# cpu.net
KiCad netlist of a schematic drawn in Altium Designer
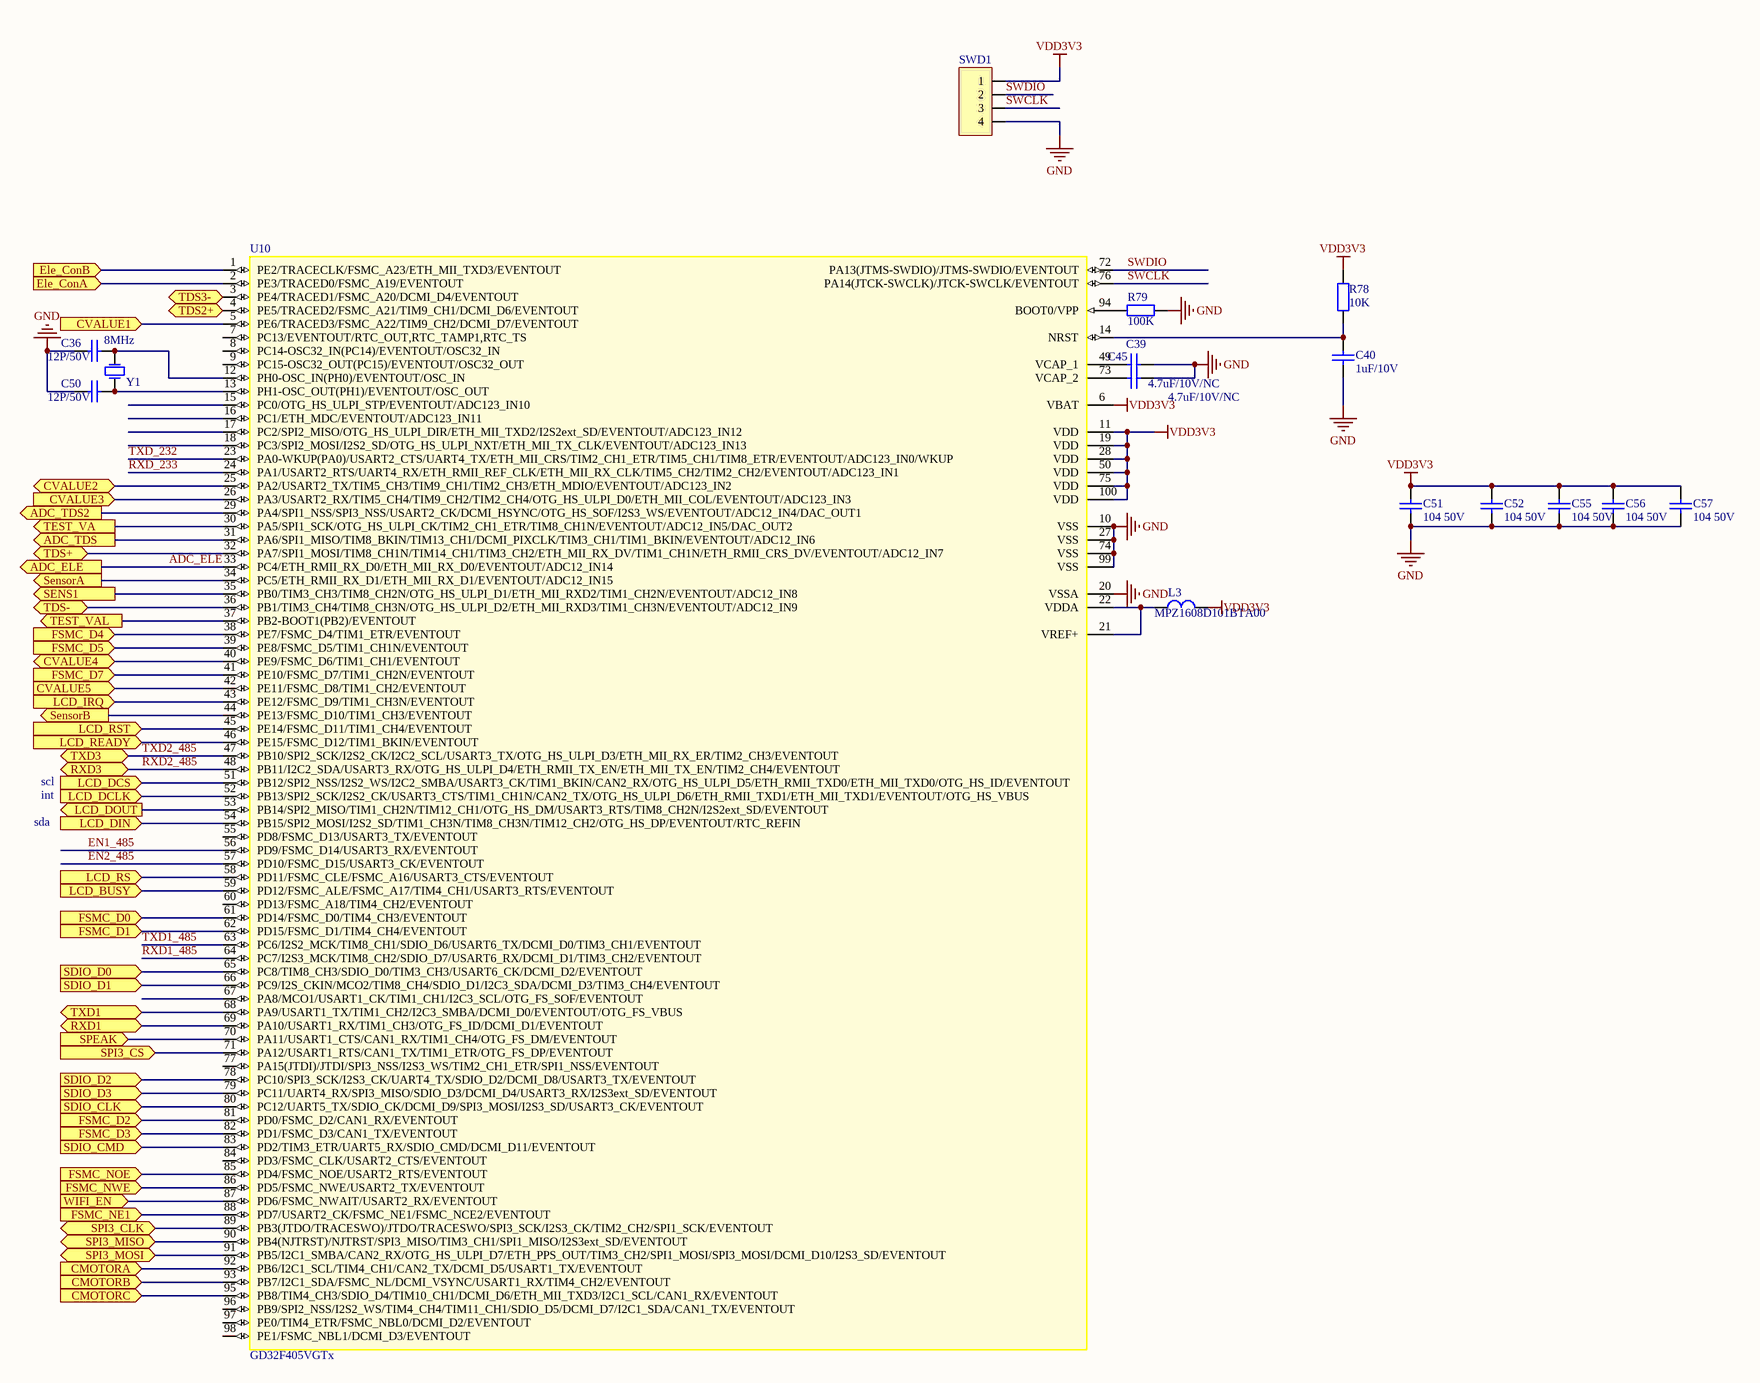
[diagram p0: cpu.SchDoc]

(export (version "E")
  (design (tool "Eeschema 10.0.6"))
  (components
    (comp (ref "C36")
      (value "12P/50V")
      (footprint "SMD-0603C")
      (description "贴片电容 5%")
      (libsource (lib "XiaoyI") (part "CAP4"))
    )
    (comp (ref "C39")
      (value "4.7uF/10V/NC")
      (footprint "SMD-0603C")
      (description "贴片电容 20%")
      (libsource (lib "XiaoyI") (part "CAP4"))
    )
    (comp (ref "C40")
      (value "1uF/10V")
      (footprint "SMD-0603C")
      (description "贴片电容 20%")
      (libsource (lib "XiaoyI") (part "CAP4"))
    )
    (comp (ref "C45")
      (value "4.7uF/10V/NC")
      (footprint "SMD-0603C")
      (description "贴片电容 20%")
      (libsource (lib "XiaoyI") (part "CAP4"))
    )
    (comp (ref "C50")
      (value "12P/50V")
      (footprint "SMD-0603C")
      (description "贴片电容 5%")
      (libsource (lib "XiaoyI") (part "CAP4"))
    )
    (comp (ref "C51")
      (value "104 50V")
      (footprint "SMD-0603C")
      (description "贴片电容 20%")
      (libsource (lib "XiaoyI") (part "CAP4"))
    )
    (comp (ref "C52")
      (value "104 50V")
      (footprint "SMD-0603C")
      (description "贴片电容 20%")
      (libsource (lib "XiaoyI") (part "CAP4"))
    )
    (comp (ref "C55")
      (value "104 50V")
      (footprint "SMD-0603C")
      (description "贴片电容 20%")
      (libsource (lib "XiaoyI") (part "CAP4"))
    )
    (comp (ref "C56")
      (value "104 50V")
      (footprint "SMD-0603C")
      (description "贴片电容 20%")
      (libsource (lib "XiaoyI") (part "CAP4"))
    )
    (comp (ref "C57")
      (value "104 50V")
      (footprint "SMD-0603C")
      (description "贴片电容 20%")
      (libsource (lib "XiaoyI") (part "CAP4"))
    )
    (comp (ref "L3")
      (value "MPZ1608D101BTA00")
      (footprint "SMD-0603")
      (description "磁珠电感 100R 100MHz")
      (libsource (lib "XiaoyI") (part "CIZHU1"))
    )
    (comp (ref "R78")
      (value "10K")
      (footprint "SMD-0603")
      (description "贴片电阻 5%")
      (libsource (lib "") (part "RES2_1"))
    )
    (comp (ref "R79")
      (value "100K")
      (footprint "SMD-0603")
      (description "贴片电阻 5%")
      (libsource (lib "XiaoyI") (part "RES2"))
    )
    (comp (ref "SWD1")
      (value "SIP-4 (NC)")
      (footprint "SIP-4")
      (description "ISP 下载")
      (libsource (lib "XiaoyI") (part "SIP-4"))
    )
    (comp (ref "U10")
      (value "GD32F405VGTx")
      (footprint "STM-LQFP100_N")
      (fields (field (name "MANUFACTURER") "STMicroelectronics") (field (name "PARTNUMBER") "STM32F405VGT6"))
      (libsource (lib "STM32F4") (part "STM32F405VGTx"))
    )
    (comp (ref "Y1")
      (value "8MHz")
      (footprint "XTAL-3225-2")
      (description "3225 贴片晶振")
      (libsource (lib "XiaoyI") (part "XTAL"))
    )
  )
  (nets
    (net (code "1") (name "/ADC_ELE") (class "Default")
      (node (ref "U10") (pin "33") (pinfunction "PC4/ETH_RMII_RX_D0/ETH_MII_RX_D0/EVENTOUT/ADC12_IN14_33") (pintype "bidirectional"))
    )
    (net (code "2") (name "/ADC_TDS") (class "Default")
      (node (ref "U10") (pin "31") (pinfunction "PA6/SPI1_MISO/TIM8_BKIN/TIM13_CH1/DCMI_PIXCLK/TIM3_CH1/TIM1_BKIN/EVENTOUT/ADC12_IN6_31") (pintype "bidirectional"))
    )
    (net (code "3") (name "/ADC_TDS2") (class "Default")
      (node (ref "U10") (pin "29") (pinfunction "PA4/SPI1_NSS/SPI3_NSS/USART2_CK/DCMI_HSYNC/OTG_HS_SOF/I2S3_WS/EVENTOUT/ADC12_IN4/DAC_OUT1_29") (pintype "bidirectional"))
    )
    (net (code "4") (name "/CMOTORA") (class "Default")
      (node (ref "U10") (pin "92") (pinfunction "PB6/I2C1_SCL/TIM4_CH1/CAN2_TX/DCMI_D5/USART1_TX/EVENTOUT_92") (pintype "bidirectional"))
    )
    (net (code "5") (name "/CMOTORB") (class "Default")
      (node (ref "U10") (pin "93") (pinfunction "PB7/I2C1_SDA/FSMC_NL/DCMI_VSYNC/USART1_RX/TIM4_CH2/EVENTOUT_93") (pintype "bidirectional"))
    )
    (net (code "6") (name "/CMOTORC") (class "Default")
      (node (ref "U10") (pin "95") (pinfunction "PB8/TIM4_CH3/SDIO_D4/TIM10_CH1/DCMI_D6/ETH_MII_TXD3/I2C1_SCL/CAN1_RX/EVENTOUT_95") (pintype "bidirectional"))
    )
    (net (code "7") (name "/CVALUE1") (class "Default")
      (node (ref "U10") (pin "5") (pinfunction "PE6/TRACED3/FSMC_A22/TIM9_CH2/DCMI_D7/EVENTOUT_5") (pintype "bidirectional"))
    )
    (net (code "8") (name "/CVALUE2") (class "Default")
      (node (ref "U10") (pin "25") (pinfunction "PA2/USART2_TX/TIM5_CH3/TIM9_CH1/TIM2_CH3/ETH_MDIO/EVENTOUT/ADC123_IN2_25") (pintype "bidirectional"))
    )
    (net (code "9") (name "/CVALUE3") (class "Default")
      (node (ref "U10") (pin "26") (pinfunction "PA3/USART2_RX/TIM5_CH4/TIM9_CH2/TIM2_CH4/OTG_HS_ULPI_D0/ETH_MII_COL/EVENTOUT/ADC123_IN3_26") (pintype "bidirectional"))
    )
    (net (code "10") (name "/CVALUE4") (class "Default")
      (node (ref "U10") (pin "40") (pinfunction "PE9/FSMC_D6/TIM1_CH1/EVENTOUT_40") (pintype "bidirectional"))
    )
    (net (code "11") (name "/CVALUE5") (class "Default")
      (node (ref "U10") (pin "42") (pinfunction "PE11/FSMC_D8/TIM1_CH2/EVENTOUT_42") (pintype "bidirectional"))
    )
    (net (code "12") (name "/EN1_485") (class "Default")
      (node (ref "U10") (pin "56") (pinfunction "PD9/FSMC_D14/USART3_RX/EVENTOUT_56") (pintype "bidirectional"))
    )
    (net (code "13") (name "/EN2_485") (class "Default")
      (node (ref "U10") (pin "57") (pinfunction "PD10/FSMC_D15/USART3_CK/EVENTOUT_57") (pintype "bidirectional"))
    )
    (net (code "14") (name "/Ele_ConA") (class "Default")
      (node (ref "U10") (pin "2") (pinfunction "PE3/TRACED0/FSMC_A19/EVENTOUT_2") (pintype "bidirectional"))
    )
    (net (code "15") (name "/Ele_ConB") (class "Default")
      (node (ref "U10") (pin "1") (pinfunction "PE2/TRACECLK/FSMC_A23/ETH_MII_TXD3/EVENTOUT_1") (pintype "bidirectional"))
    )
    (net (code "16") (name "/FSMC_D0") (class "Default")
      (node (ref "U10") (pin "61") (pinfunction "PD14/FSMC_D0/TIM4_CH3/EVENTOUT_61") (pintype "bidirectional"))
    )
    (net (code "17") (name "/FSMC_D1") (class "Default")
      (node (ref "U10") (pin "62") (pinfunction "PD15/FSMC_D1/TIM4_CH4/EVENTOUT_62") (pintype "bidirectional"))
    )
    (net (code "18") (name "/FSMC_D2") (class "Default")
      (node (ref "U10") (pin "81") (pinfunction "PD0/FSMC_D2/CAN1_RX/EVENTOUT_81") (pintype "bidirectional"))
    )
    (net (code "19") (name "/FSMC_D3") (class "Default")
      (node (ref "U10") (pin "82") (pinfunction "PD1/FSMC_D3/CAN1_TX/EVENTOUT_82") (pintype "bidirectional"))
    )
    (net (code "20") (name "/FSMC_D4") (class "Default")
      (node (ref "U10") (pin "38") (pinfunction "PE7/FSMC_D4/TIM1_ETR/EVENTOUT_38") (pintype "bidirectional"))
    )
    (net (code "21") (name "/FSMC_D5") (class "Default")
      (node (ref "U10") (pin "39") (pinfunction "PE8/FSMC_D5/TIM1_CH1N/EVENTOUT_39") (pintype "bidirectional"))
    )
    (net (code "22") (name "/FSMC_D7") (class "Default")
      (node (ref "U10") (pin "41") (pinfunction "PE10/FSMC_D7/TIM1_CH2N/EVENTOUT_41") (pintype "bidirectional"))
    )
    (net (code "23") (name "/FSMC_NE1") (class "Default")
      (node (ref "U10") (pin "88") (pinfunction "PD7/USART2_CK/FSMC_NE1/FSMC_NCE2/EVENTOUT_88") (pintype "bidirectional"))
    )
    (net (code "24") (name "/FSMC_NOE") (class "Default")
      (node (ref "U10") (pin "85") (pinfunction "PD4/FSMC_NOE/USART2_RTS/EVENTOUT_85") (pintype "bidirectional"))
    )
    (net (code "25") (name "/FSMC_NWE") (class "Default")
      (node (ref "U10") (pin "86") (pinfunction "PD5/FSMC_NWE/USART2_TX/EVENTOUT_86") (pintype "bidirectional"))
    )
    (net (code "26") (name "/LCD_BUSY") (class "Default")
      (node (ref "U10") (pin "59") (pinfunction "PD12/FSMC_ALE/FSMC_A17/TIM4_CH1/USART3_RTS/EVENTOUT_59") (pintype "bidirectional"))
    )
    (net (code "27") (name "/LCD_DCLK") (class "Default")
      (node (ref "U10") (pin "52") (pinfunction "PB13/SPI2_SCK/I2S2_CK/USART3_CTS/TIM1_CH1N/CAN2_TX/OTG_HS_ULPI_D6/ETH_RMII_TXD1/ETH_MII_TXD1/EVENTOUT/OTG_HS_VBUS_52") (pintype "bidirectional"))
    )
    (net (code "28") (name "/LCD_DCS") (class "Default")
      (node (ref "U10") (pin "51") (pinfunction "PB12/SPI2_NSS/I2S2_WS/I2C2_SMBA/USART3_CK/TIM1_BKIN/CAN2_RX/OTG_HS_ULPI_D5/ETH_RMII_TXD0/ETH_MII_TXD0/OTG_HS_ID/EVENTOUT_51") (pintype "bidirectional"))
    )
    (net (code "29") (name "/LCD_DIN") (class "Default")
      (node (ref "U10") (pin "54") (pinfunction "PB15/SPI2_MOSI/I2S2_SD/TIM1_CH3N/TIM8_CH3N/TIM12_CH2/OTG_HS_DP/EVENTOUT/RTC_REFIN_54") (pintype "bidirectional"))
    )
    (net (code "30") (name "/LCD_DOUT") (class "Default")
      (node (ref "U10") (pin "53") (pinfunction "PB14/SPI2_MISO/TIM1_CH2N/TIM12_CH1/OTG_HS_DM/USART3_RTS/TIM8_CH2N/I2S2ext_SD/EVENTOUT_53") (pintype "bidirectional"))
    )
    (net (code "31") (name "/LCD_IRQ") (class "Default")
      (node (ref "U10") (pin "43") (pinfunction "PE12/FSMC_D9/TIM1_CH3N/EVENTOUT_43") (pintype "bidirectional"))
    )
    (net (code "32") (name "/LCD_READY") (class "Default")
      (node (ref "U10") (pin "46") (pinfunction "PE15/FSMC_D12/TIM1_BKIN/EVENTOUT_46") (pintype "bidirectional"))
    )
    (net (code "33") (name "/LCD_RS") (class "Default")
      (node (ref "U10") (pin "58") (pinfunction "PD11/FSMC_CLE/FSMC_A16/USART3_CTS/EVENTOUT_58") (pintype "bidirectional"))
    )
    (net (code "34") (name "/LCD_RST") (class "Default")
      (node (ref "U10") (pin "45") (pinfunction "PE14/FSMC_D11/TIM1_CH4/EVENTOUT_45") (pintype "bidirectional"))
    )
    (net (code "35") (name "/RXD1") (class "Default")
      (node (ref "U10") (pin "69") (pinfunction "PA10/USART1_RX/TIM1_CH3/OTG_FS_ID/DCMI_D1/EVENTOUT_69") (pintype "bidirectional"))
    )
    (net (code "36") (name "/RXD1_485") (class "Default")
      (node (ref "U10") (pin "64") (pinfunction "PC7/I2S3_MCK/TIM8_CH2/SDIO_D7/USART6_RX/DCMI_D1/TIM3_CH2/EVENTOUT_64") (pintype "bidirectional"))
    )
    (net (code "37") (name "/RXD2_485") (class "Default")
      (node (ref "U10") (pin "48") (pinfunction "PB11/I2C2_SDA/USART3_RX/OTG_HS_ULPI_D4/ETH_RMII_TX_EN/ETH_MII_TX_EN/TIM2_CH4/EVENTOUT_48") (pintype "bidirectional"))
    )
    (net (code "38") (name "/RXD_233") (class "Default")
      (node (ref "U10") (pin "24") (pinfunction "PA1/USART2_RTS/UART4_RX/ETH_RMII_REF_CLK/ETH_MII_RX_CLK/TIM5_CH2/TIM2_CH2/EVENTOUT/ADC123_IN1_24") (pintype "bidirectional"))
    )
    (net (code "39") (name "/SDIO_CLK") (class "Default")
      (node (ref "U10") (pin "80") (pinfunction "PC12/UART5_TX/SDIO_CK/DCMI_D9/SPI3_MOSI/I2S3_SD/USART3_CK/EVENTOUT_80") (pintype "bidirectional"))
    )
    (net (code "40") (name "/SDIO_CMD") (class "Default")
      (node (ref "U10") (pin "83") (pinfunction "PD2/TIM3_ETR/UART5_RX/SDIO_CMD/DCMI_D11/EVENTOUT_83") (pintype "bidirectional"))
    )
    (net (code "41") (name "/SDIO_D0") (class "Default")
      (node (ref "U10") (pin "65") (pinfunction "PC8/TIM8_CH3/SDIO_D0/TIM3_CH3/USART6_CK/DCMI_D2/EVENTOUT_65") (pintype "bidirectional"))
    )
    (net (code "42") (name "/SDIO_D1") (class "Default")
      (node (ref "U10") (pin "66") (pinfunction "PC9/I2S_CKIN/MCO2/TIM8_CH4/SDIO_D1/I2C3_SDA/DCMI_D3/TIM3_CH4/EVENTOUT_66") (pintype "bidirectional"))
    )
    (net (code "43") (name "/SDIO_D2") (class "Default")
      (node (ref "U10") (pin "78") (pinfunction "PC10/SPI3_SCK/I2S3_CK/UART4_TX/SDIO_D2/DCMI_D8/USART3_TX/EVENTOUT_78") (pintype "bidirectional"))
    )
    (net (code "44") (name "/SDIO_D3") (class "Default")
      (node (ref "U10") (pin "79") (pinfunction "PC11/UART4_RX/SPI3_MISO/SDIO_D3/DCMI_D4/USART3_RX/I2S3ext_SD/EVENTOUT_79") (pintype "bidirectional"))
    )
    (net (code "45") (name "/SENS1") (class "Default")
      (node (ref "U10") (pin "35") (pinfunction "PB0/TIM3_CH3/TIM8_CH2N/OTG_HS_ULPI_D1/ETH_MII_RXD2/TIM1_CH2N/EVENTOUT/ADC12_IN8_35") (pintype "bidirectional"))
    )
    (net (code "46") (name "/SPEAK") (class "Default")
      (node (ref "U10") (pin "70") (pinfunction "PA11/USART1_CTS/CAN1_RX/TIM1_CH4/OTG_FS_DM/EVENTOUT_70") (pintype "bidirectional"))
    )
    (net (code "47") (name "/SPI3_CLK") (class "Default")
      (node (ref "U10") (pin "89") (pinfunction "PB3(JTDO/TRACESWO)/JTDO/TRACESWO/SPI3_SCK/I2S3_CK/TIM2_CH2/SPI1_SCK/EVENTOUT_89") (pintype "bidirectional"))
    )
    (net (code "48") (name "/SPI3_CS") (class "Default")
      (node (ref "U10") (pin "71") (pinfunction "PA12/USART1_RTS/CAN1_TX/TIM1_ETR/OTG_FS_DP/EVENTOUT_71") (pintype "bidirectional"))
    )
    (net (code "49") (name "/SPI3_MISO") (class "Default")
      (node (ref "U10") (pin "90") (pinfunction "PB4(NJTRST)/NJTRST/SPI3_MISO/TIM3_CH1/SPI1_MISO/I2S3ext_SD/EVENTOUT_90") (pintype "bidirectional"))
    )
    (net (code "50") (name "/SPI3_MOSI") (class "Default")
      (node (ref "U10") (pin "91") (pinfunction "PB5/I2C1_SMBA/CAN2_RX/OTG_HS_ULPI_D7/ETH_PPS_OUT/TIM3_CH2/SPI1_MOSI/SPI3_MOSI/DCMI_D10/I2S3_SD/EVENTOUT_91") (pintype "bidirectional"))
    )
    (net (code "51") (name "/SWCLK") (class "Default")
      (node (ref "SWD1") (pin "3") (pinfunction "3_3") (pintype "passive"))
      (node (ref "U10") (pin "76") (pinfunction "PA14(JTCK-SWCLK)/JTCK-SWCLK/EVENTOUT_76") (pintype "bidirectional"))
    )
    (net (code "52") (name "/SWDIO") (class "Default")
      (node (ref "SWD1") (pin "2") (pinfunction "2_2") (pintype "passive"))
      (node (ref "U10") (pin "72") (pinfunction "PA13(JTMS-SWDIO)/JTMS-SWDIO/EVENTOUT_72") (pintype "bidirectional"))
    )
    (net (code "53") (name "/SensorA") (class "Default")
      (node (ref "U10") (pin "34") (pinfunction "PC5/ETH_RMII_RX_D1/ETH_MII_RX_D1/EVENTOUT/ADC12_IN15_34") (pintype "bidirectional"))
    )
    (net (code "54") (name "/SensorB") (class "Default")
      (node (ref "U10") (pin "44") (pinfunction "PE13/FSMC_D10/TIM1_CH3/EVENTOUT_44") (pintype "bidirectional"))
    )
    (net (code "55") (name "/TDS+") (class "Default")
      (node (ref "U10") (pin "32") (pinfunction "PA7/SPI1_MOSI/TIM8_CH1N/TIM14_CH1/TIM3_CH2/ETH_MII_RX_DV/TIM1_CH1N/ETH_RMII_CRS_DV/EVENTOUT/ADC12_IN7_32") (pintype "bidirectional"))
    )
    (net (code "56") (name "/TDS-") (class "Default")
      (node (ref "U10") (pin "36") (pinfunction "PB1/TIM3_CH4/TIM8_CH3N/OTG_HS_ULPI_D2/ETH_MII_RXD3/TIM1_CH3N/EVENTOUT/ADC12_IN9_36") (pintype "bidirectional"))
    )
    (net (code "57") (name "/TDS2+") (class "Default")
      (node (ref "U10") (pin "4") (pinfunction "PE5/TRACED2/FSMC_A21/TIM9_CH1/DCMI_D6/EVENTOUT_4") (pintype "bidirectional"))
    )
    (net (code "58") (name "/TDS3-") (class "Default")
      (node (ref "U10") (pin "3") (pinfunction "PE4/TRACED1/FSMC_A20/DCMI_D4/EVENTOUT_3") (pintype "bidirectional"))
    )
    (net (code "59") (name "/TEST_VA") (class "Default")
      (node (ref "U10") (pin "30") (pinfunction "PA5/SPI1_SCK/OTG_HS_ULPI_CK/TIM2_CH1_ETR/TIM8_CH1N/EVENTOUT/ADC12_IN5/DAC_OUT2_30") (pintype "bidirectional"))
    )
    (net (code "60") (name "/TEST_VAL") (class "Default")
      (node (ref "U10") (pin "37") (pinfunction "PB2-BOOT1(PB2)/EVENTOUT_37") (pintype "bidirectional"))
    )
    (net (code "61") (name "/TXD1") (class "Default")
      (node (ref "U10") (pin "68") (pinfunction "PA9/USART1_TX/TIM1_CH2/I2C3_SMBA/DCMI_D0/EVENTOUT/OTG_FS_VBUS_68") (pintype "bidirectional"))
    )
    (net (code "62") (name "/TXD1_485") (class "Default")
      (node (ref "U10") (pin "63") (pinfunction "PC6/I2S2_MCK/TIM8_CH1/SDIO_D6/USART6_TX/DCMI_D0/TIM3_CH1/EVENTOUT_63") (pintype "bidirectional"))
    )
    (net (code "63") (name "/TXD2_485") (class "Default")
      (node (ref "U10") (pin "47") (pinfunction "PB10/SPI2_SCK/I2S2_CK/I2C2_SCL/USART3_TX/OTG_HS_ULPI_D3/ETH_MII_RX_ER/TIM2_CH3/EVENTOUT_47") (pintype "bidirectional"))
    )
    (net (code "64") (name "/TXD_232") (class "Default")
      (node (ref "U10") (pin "23") (pinfunction "PA0-WKUP(PA0)/USART2_CTS/UART4_TX/ETH_MII_CRS/TIM2_CH1_ETR/TIM5_CH1/TIM8_ETR/EVENTOUT/ADC123_IN0/WKUP_23") (pintype "bidirectional"))
    )
    (net (code "65") (name "/WIFI_EN") (class "Default")
      (node (ref "U10") (pin "87") (pinfunction "PD6/FSMC_NWAIT/USART2_RX/EVENTOUT_87") (pintype "bidirectional"))
    )
    (net (code "66") (name "GND") (class "Default")
      (node (ref "C36") (pin "2") (pinfunction "2_2") (pintype "passive"))
      (node (ref "C39") (pin "1") (pinfunction "1_1") (pintype "passive"))
      (node (ref "C40") (pin "1") (pinfunction "1_1") (pintype "passive"))
      (node (ref "C45") (pin "1") (pinfunction "1_1") (pintype "passive"))
      (node (ref "C50") (pin "2") (pinfunction "2_2") (pintype "passive"))
      (node (ref "C51") (pin "1") (pinfunction "1_1") (pintype "passive"))
      (node (ref "C52") (pin "1") (pinfunction "1_1") (pintype "passive"))
      (node (ref "C55") (pin "1") (pinfunction "1_1") (pintype "passive"))
      (node (ref "C56") (pin "1") (pinfunction "1_1") (pintype "passive"))
      (node (ref "C57") (pin "1") (pinfunction "1_1") (pintype "passive"))
      (node (ref "R79") (pin "1") (pinfunction "1_1") (pintype "passive"))
      (node (ref "SWD1") (pin "4") (pinfunction "4_4") (pintype "passive"))
      (node (ref "U10") (pin "10") (pinfunction "VSS_10") (pintype "power_in"))
      (node (ref "U10") (pin "20") (pinfunction "VSSA_20") (pintype "power_in"))
      (node (ref "U10") (pin "27") (pinfunction "VSS_27") (pintype "power_in"))
      (node (ref "U10") (pin "74") (pinfunction "VSS_74") (pintype "power_in"))
      (node (ref "U10") (pin "99") (pinfunction "VSS_99") (pintype "power_in"))
    )
    (net (code "67") (name "Net-(U10-BOOT0{slash}VPP)") (class "Default")
      (node (ref "R79") (pin "2") (pinfunction "2_2") (pintype "passive"))
      (node (ref "U10") (pin "94") (pinfunction "BOOT0/VPP_94") (pintype "input"))
    )
    (net (code "68") (name "Net-(U10-NRST)") (class "Default")
      (node (ref "C40") (pin "2") (pinfunction "2_2") (pintype "passive"))
      (node (ref "R78") (pin "1") (pinfunction "1_1") (pintype "passive"))
      (node (ref "U10") (pin "14") (pinfunction "NRST_14") (pintype "bidirectional"))
    )
    (net (code "69") (name "Net-(U10-PH0-OSC_IN(PH0){slash}EVENTOUT{slash}OSC_IN)") (class "Default")
      (node (ref "C36") (pin "1") (pinfunction "1_1") (pintype "passive"))
      (node (ref "U10") (pin "12") (pinfunction "PH0-OSC_IN(PH0)/EVENTOUT/OSC_IN_12") (pintype "bidirectional"))
      (node (ref "Y1") (pin "2") (pinfunction "OSC2_2") (pintype "passive"))
    )
    (net (code "70") (name "Net-(U10-PH1-OSC_OUT(PH1){slash}EVENTOUT{slash}OSC_OUT)") (class "Default")
      (node (ref "C50") (pin "1") (pinfunction "1_1") (pintype "passive"))
      (node (ref "U10") (pin "13") (pinfunction "PH1-OSC_OUT(PH1)/EVENTOUT/OSC_OUT_13") (pintype "bidirectional"))
      (node (ref "Y1") (pin "1") (pinfunction "OSC1_1") (pintype "passive"))
    )
    (net (code "71") (name "Net-(U10-VCAP_1)") (class "Default")
      (node (ref "C39") (pin "2") (pinfunction "2_2") (pintype "passive"))
      (node (ref "U10") (pin "49") (pinfunction "VCAP_1_49") (pintype "power_in"))
    )
    (net (code "72") (name "Net-(U10-VCAP_2)") (class "Default")
      (node (ref "C45") (pin "2") (pinfunction "2_2") (pintype "passive"))
      (node (ref "U10") (pin "73") (pinfunction "VCAP_2_73") (pintype "power_in"))
    )
    (net (code "73") (name "Net-(U10-VDDA)") (class "Default")
      (node (ref "L3") (pin "2") (pinfunction "2_2") (pintype "passive"))
      (node (ref "U10") (pin "21") (pinfunction "VREF+_21") (pintype "power_in"))
      (node (ref "U10") (pin "22") (pinfunction "VDDA_22") (pintype "power_in"))
    )
    (net (code "74") (name "VDD3V3") (class "Default")
      (node (ref "C51") (pin "2") (pinfunction "2_2") (pintype "passive"))
      (node (ref "C52") (pin "2") (pinfunction "2_2") (pintype "passive"))
      (node (ref "C55") (pin "2") (pinfunction "2_2") (pintype "passive"))
      (node (ref "C56") (pin "2") (pinfunction "2_2") (pintype "passive"))
      (node (ref "C57") (pin "2") (pinfunction "2_2") (pintype "passive"))
      (node (ref "L3") (pin "1") (pinfunction "1_1") (pintype "passive"))
      (node (ref "R78") (pin "2") (pinfunction "2_2") (pintype "passive"))
      (node (ref "SWD1") (pin "1") (pinfunction "1_1") (pintype "passive"))
      (node (ref "U10") (pin "100") (pinfunction "VDD_100") (pintype "power_in"))
      (node (ref "U10") (pin "11") (pinfunction "VDD_11") (pintype "power_in"))
      (node (ref "U10") (pin "19") (pinfunction "VDD_19") (pintype "power_in"))
      (node (ref "U10") (pin "28") (pinfunction "VDD_28") (pintype "power_in"))
      (node (ref "U10") (pin "50") (pinfunction "VDD_50") (pintype "power_in"))
      (node (ref "U10") (pin "6") (pinfunction "VBAT_6") (pintype "power_in"))
      (node (ref "U10") (pin "75") (pinfunction "VDD_75") (pintype "power_in"))
    )
    (net (code "75") (name "unconnected-(U10-PA8{slash}MCO1{slash}USART1_CK{slash}TIM1_CH1{slash}I2C3_SCL{slash}OTG_FS_SOF{slash}EVENTOUT-Pad67)") (class "Default")
      (node (ref "U10") (pin "67") (pinfunction "PA8/MCO1/USART1_CK/TIM1_CH1/I2C3_SCL/OTG_FS_SOF/EVENTOUT_67") (pintype "bidirectional"))
    )
    (net (code "76") (name "unconnected-(U10-PA15(JTDI){slash}JTDI{slash}SPI3_NSS{slash}I2S3_WS{slash}TIM2_CH1_ETR{slash}SPI1_NSS{slash}EVENTOUT-Pad77)") (class "Default")
      (node (ref "U10") (pin "77") (pinfunction "PA15(JTDI)/JTDI/SPI3_NSS/I2S3_WS/TIM2_CH1_ETR/SPI1_NSS/EVENTOUT_77") (pintype "bidirectional"))
    )
    (net (code "77") (name "unconnected-(U10-PB9{slash}SPI2_NSS{slash}I2S2_WS{slash}TIM4_CH4{slash}TIM11_CH1{slash}SDIO_D5{slash}DCMI_D7{slash}I2C1_SDA{slash}CAN1_TX{slash}EVENTOUT-Pad96)") (class "Default")
      (node (ref "U10") (pin "96") (pinfunction "PB9/SPI2_NSS/I2S2_WS/TIM4_CH4/TIM11_CH1/SDIO_D5/DCMI_D7/I2C1_SDA/CAN1_TX/EVENTOUT_96") (pintype "bidirectional"))
    )
    (net (code "78") (name "unconnected-(U10-PC0{slash}OTG_HS_ULPI_STP{slash}EVENTOUT{slash}ADC123_IN10-Pad15)") (class "Default")
      (node (ref "U10") (pin "15") (pinfunction "PC0/OTG_HS_ULPI_STP/EVENTOUT/ADC123_IN10_15") (pintype "bidirectional"))
    )
    (net (code "79") (name "unconnected-(U10-PC1{slash}ETH_MDC{slash}EVENTOUT{slash}ADC123_IN11-Pad16)") (class "Default")
      (node (ref "U10") (pin "16") (pinfunction "PC1/ETH_MDC/EVENTOUT/ADC123_IN11_16") (pintype "bidirectional"))
    )
    (net (code "80") (name "unconnected-(U10-PC2{slash}SPI2_MISO{slash}OTG_HS_ULPI_DIR{slash}ETH_MII_TXD2{slash}I2S2ext_SD{slash}EVENTOUT{slash}ADC123_IN12-Pad17)") (class "Default")
      (node (ref "U10") (pin "17") (pinfunction "PC2/SPI2_MISO/OTG_HS_ULPI_DIR/ETH_MII_TXD2/I2S2ext_SD/EVENTOUT/ADC123_IN12_17") (pintype "bidirectional"))
    )
    (net (code "81") (name "unconnected-(U10-PC3{slash}SPI2_MOSI{slash}I2S2_SD{slash}OTG_HS_ULPI_NXT{slash}ETH_MII_TX_CLK{slash}EVENTOUT{slash}ADC123_IN13-Pad18)") (class "Default")
      (node (ref "U10") (pin "18") (pinfunction "PC3/SPI2_MOSI/I2S2_SD/OTG_HS_ULPI_NXT/ETH_MII_TX_CLK/EVENTOUT/ADC123_IN13_18") (pintype "bidirectional"))
    )
    (net (code "82") (name "unconnected-(U10-PC13{slash}EVENTOUT{slash}RTC_OUT,RTC_TAMP1,RTC_TS-Pad7)") (class "Default")
      (node (ref "U10") (pin "7") (pinfunction "PC13/EVENTOUT/RTC_OUT,RTC_TAMP1,RTC_TS_7") (pintype "bidirectional"))
    )
    (net (code "83") (name "unconnected-(U10-PC14-OSC32_IN(PC14){slash}EVENTOUT{slash}OSC32_IN-Pad8)") (class "Default")
      (node (ref "U10") (pin "8") (pinfunction "PC14-OSC32_IN(PC14)/EVENTOUT/OSC32_IN_8") (pintype "bidirectional"))
    )
    (net (code "84") (name "unconnected-(U10-PC15-OSC32_OUT(PC15){slash}EVENTOUT{slash}OSC32_OUT-Pad9)") (class "Default")
      (node (ref "U10") (pin "9") (pinfunction "PC15-OSC32_OUT(PC15)/EVENTOUT/OSC32_OUT_9") (pintype "bidirectional"))
    )
    (net (code "85") (name "unconnected-(U10-PD3{slash}FSMC_CLK{slash}USART2_CTS{slash}EVENTOUT-Pad84)") (class "Default")
      (node (ref "U10") (pin "84") (pinfunction "PD3/FSMC_CLK/USART2_CTS/EVENTOUT_84") (pintype "bidirectional"))
    )
    (net (code "86") (name "unconnected-(U10-PD8{slash}FSMC_D13{slash}USART3_TX{slash}EVENTOUT-Pad55)") (class "Default")
      (node (ref "U10") (pin "55") (pinfunction "PD8/FSMC_D13/USART3_TX/EVENTOUT_55") (pintype "bidirectional"))
    )
    (net (code "87") (name "unconnected-(U10-PD13{slash}FSMC_A18{slash}TIM4_CH2{slash}EVENTOUT-Pad60)") (class "Default")
      (node (ref "U10") (pin "60") (pinfunction "PD13/FSMC_A18/TIM4_CH2/EVENTOUT_60") (pintype "bidirectional"))
    )
    (net (code "88") (name "unconnected-(U10-PE0{slash}TIM4_ETR{slash}FSMC_NBL0{slash}DCMI_D2{slash}EVENTOUT-Pad97)") (class "Default")
      (node (ref "U10") (pin "97") (pinfunction "PE0/TIM4_ETR/FSMC_NBL0/DCMI_D2/EVENTOUT_97") (pintype "bidirectional"))
    )
    (net (code "89") (name "unconnected-(U10-PE1{slash}FSMC_NBL1{slash}DCMI_D3{slash}EVENTOUT-Pad98)") (class "Default")
      (node (ref "U10") (pin "98") (pinfunction "PE1/FSMC_NBL1/DCMI_D3/EVENTOUT_98") (pintype "bidirectional"))
    )
  )
)
